# pendant.net
KiCad netlist of a schematic drawn in EAGLE
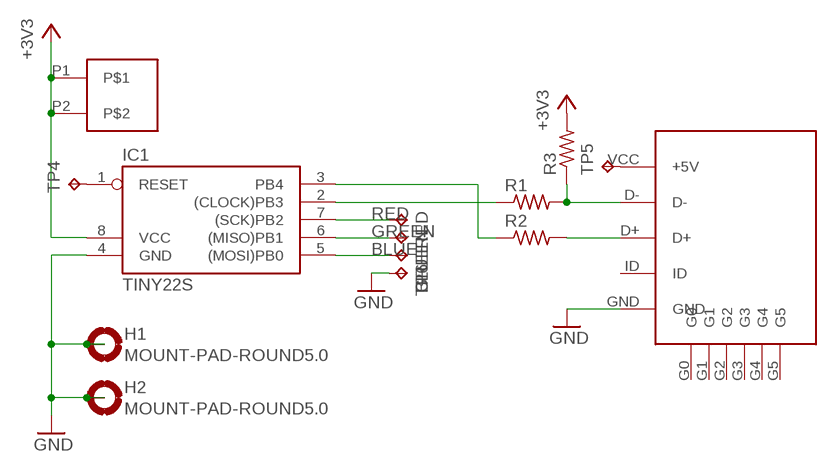
[diagram p0: schematic, sheet 1]

(export (version "E")
  (design (tool "Eeschema 10.0.6"))
  (components
    (comp (ref "BLUE")
      (value "TPPAD1-13")
      (footprint "eagle-import:P1-13")
      (libsource (lib "eagle-import") (part "TPPAD1-13"))
    )
    (comp (ref "GREEN")
      (value "TPPAD1-13")
      (footprint "eagle-import:P1-13")
      (libsource (lib "eagle-import") (part "TPPAD1-13"))
    )
    (comp (ref "H1")
      (value "MOUNT-PAD-ROUND5.0")
      (footprint "eagle-import:5,0-PAD")
      (libsource (lib "eagle-import") (part "MOUNT-PAD-ROUND5.0"))
    )
    (comp (ref "H2")
      (value "MOUNT-PAD-ROUND5.0")
      (footprint "eagle-import:5,0-PAD")
      (libsource (lib "eagle-import") (part "MOUNT-PAD-ROUND5.0"))
    )
    (comp (ref "IC1")
      (value "TINY22S")
      (footprint "eagle-import:SOIC8")
      (libsource (lib "eagle-import") (part "TINY22S"))
    )
    (comp (ref "R1")
      (value "R-US_R0603")
      (footprint "eagle-import:R0603")
      (libsource (lib "eagle-import") (part "R-US_R0603"))
    )
    (comp (ref "R2")
      (value "R-US_R0603")
      (footprint "eagle-import:R0603")
      (libsource (lib "eagle-import") (part "R-US_R0603"))
    )
    (comp (ref "R3")
      (value "R-US_R0603")
      (footprint "eagle-import:R0603")
      (libsource (lib "eagle-import") (part "R-US_R0603"))
    )
    (comp (ref "RED")
      (value "TPPAD1-13")
      (footprint "eagle-import:P1-13")
      (libsource (lib "eagle-import") (part "TPPAD1-13"))
    )
    (comp (ref "TP4")
      (value "TPPAD1-13")
      (footprint "eagle-import:P1-13")
      (libsource (lib "eagle-import") (part "TPPAD1-13"))
    )
    (comp (ref "TP5")
      (value "TPTP10SQ")
      (footprint "eagle-import:TP10SQ")
      (libsource (lib "eagle-import") (part "TPTP10SQ"))
    )
    (comp (ref "TP6")
      (value "TPPAD1-13")
      (footprint "eagle-import:P1-13")
      (libsource (lib "eagle-import") (part "TPPAD1-13"))
    )
    (comp (ref "U$1")
      (value "USB-MICRO")
      (footprint "eagle-import:UB-MC5BR3-M404")
      (libsource (lib "eagle-import") (part "USB-MICRO"))
    )
    (comp (ref "U$2")
      (value "MAGNET8TH-INCH")
      (footprint "eagle-import:8TH-SQUARE")
      (libsource (lib "eagle-import") (part "MAGNET8TH-INCH"))
    )
  )
  (nets
    (net (code "1") (name "+3V3") (class "Default")
      (node (ref "IC1") (pin "8") (pinfunction "VCC_8") (pintype "power_in"))
      (node (ref "R3") (pin "2") (pinfunction "2_2") (pintype "passive"))
      (node (ref "U$2") (pin "P1") (pinfunction "P$1_P1") (pintype "power_in"))
      (node (ref "U$2") (pin "P2") (pinfunction "P$2_P2") (pintype "power_in"))
    )
    (net (code "2") (name "/BLUE") (class "Default")
      (node (ref "BLUE") (pin "TP") (pinfunction "TP_TP") (pintype "input"))
      (node (ref "IC1") (pin "5") (pinfunction "(MOSI)PB0_5") (pintype "bidirectional"))
    )
    (net (code "3") (name "/G0") (class "Default")
      (node (ref "U$1") (pin "G0") (pinfunction "G0_G0") (pintype "power_in"))
    )
    (net (code "4") (name "/G1") (class "Default")
      (node (ref "U$1") (pin "G1") (pinfunction "G1_G1") (pintype "power_in"))
    )
    (net (code "5") (name "/G2") (class "Default")
      (node (ref "U$1") (pin "G2") (pinfunction "G2_G2") (pintype "power_in"))
    )
    (net (code "6") (name "/G3") (class "Default")
      (node (ref "U$1") (pin "G3") (pinfunction "G3_G3") (pintype "power_in"))
    )
    (net (code "7") (name "/G4") (class "Default")
      (node (ref "U$1") (pin "G4") (pinfunction "G4_G4") (pintype "power_in"))
    )
    (net (code "8") (name "/G5") (class "Default")
      (node (ref "U$1") (pin "G5") (pinfunction "G5_G5") (pintype "power_in"))
    )
    (net (code "9") (name "/GREEN") (class "Default")
      (node (ref "GREEN") (pin "TP") (pinfunction "TP_TP") (pintype "input"))
      (node (ref "IC1") (pin "6") (pinfunction "(MISO)PB1_6") (pintype "bidirectional"))
    )
    (net (code "10") (name "/RED") (class "Default")
      (node (ref "IC1") (pin "7") (pinfunction "(SCK)PB2_7") (pintype "bidirectional"))
      (node (ref "RED") (pin "TP") (pinfunction "TP_TP") (pintype "input"))
    )
    (net (code "11") (name "GND") (class "Default")
      (node (ref "H1") (pin "B5") (pinfunction "MOUNT_B5") (pintype "passive"))
      (node (ref "H2") (pin "B5") (pinfunction "MOUNT_B5") (pintype "passive"))
      (node (ref "IC1") (pin "4") (pinfunction "GND_4") (pintype "power_in"))
      (node (ref "TP6") (pin "TP") (pinfunction "TP_TP") (pintype "input"))
      (node (ref "U$1") (pin "GND") (pinfunction "GND_GND") (pintype "power_in"))
    )
    (net (code "12") (name "Net-(IC1-(CLOCK)PB3)") (class "Default")
      (node (ref "IC1") (pin "2") (pinfunction "(CLOCK)PB3_2") (pintype "bidirectional"))
      (node (ref "R1") (pin "1") (pinfunction "1_1") (pintype "passive"))
    )
    (net (code "13") (name "Net-(IC1-PB4)") (class "Default")
      (node (ref "IC1") (pin "3") (pinfunction "PB4_3") (pintype "bidirectional"))
      (node (ref "R2") (pin "1") (pinfunction "1_1") (pintype "passive"))
    )
    (net (code "14") (name "Net-(IC1-RESET)") (class "Default")
      (node (ref "IC1") (pin "1") (pinfunction "RESET_1") (pintype "input"))
      (node (ref "TP4") (pin "TP") (pinfunction "TP_TP") (pintype "input"))
    )
    (net (code "15") (name "Net-(R1-Pad2)") (class "Default")
      (node (ref "R1") (pin "2") (pinfunction "2_2") (pintype "passive"))
      (node (ref "R3") (pin "1") (pinfunction "1_1") (pintype "passive"))
      (node (ref "U$1") (pin "D-") (pinfunction "D-_D-") (pintype "bidirectional"))
    )
    (net (code "16") (name "Net-(R2-Pad2)") (class "Default")
      (node (ref "R2") (pin "2") (pinfunction "2_2") (pintype "passive"))
      (node (ref "U$1") (pin "D+") (pinfunction "D+_D+") (pintype "bidirectional"))
    )
    (net (code "17") (name "Net-(U$1-+5V)") (class "Default")
      (node (ref "TP5") (pin "TP") (pinfunction "TP_TP") (pintype "input"))
      (node (ref "U$1") (pin "VCC") (pinfunction "+5V_VCC") (pintype "power_in"))
    )
    (net (code "18") (name "unconnected-(U$1-PadID)") (class "Default")
      (node (ref "U$1") (pin "ID") (pinfunction "ID_ID") (pintype "bidirectional"))
    )
  )
)
